# BRAIN_2.net
KiCad netlist of a schematic drawn in EAGLE
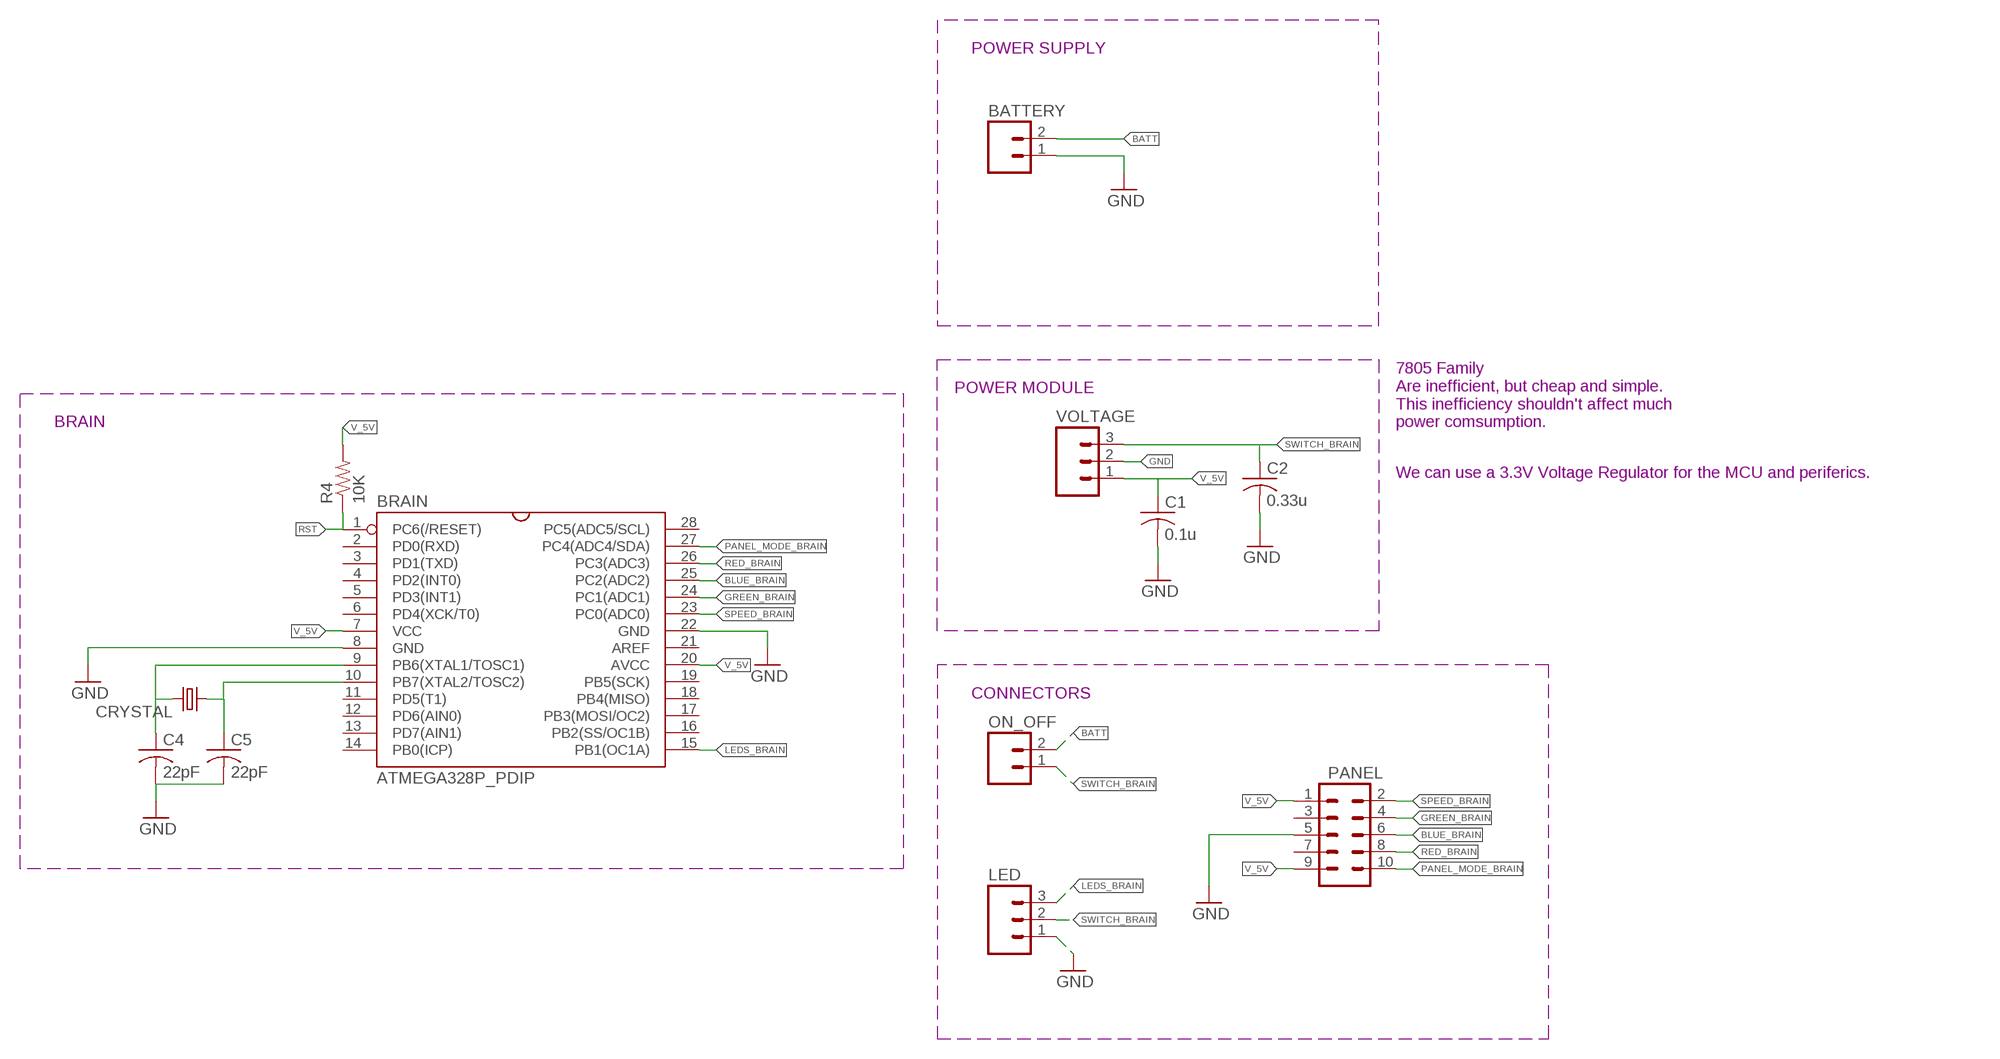
[diagram p0: schematic, sheet 1]

(export (version "E")
  (design (tool "Eeschema 10.0.6"))
  (components
    (comp (ref "BATTERY")
      (value "M02PTH")
      (footprint "eagle-import:1X02")
      (libsource (lib "eagle-import") (part "M02PTH"))
    )
    (comp (ref "BRAIN")
      (value "ATMEGA328P_PDIP")
      (footprint "eagle-import:DIL-28-3")
      (libsource (lib "eagle-import") (part "ATMEGA328P_PDIP"))
    )
    (comp (ref "C1")
      (value "0.1u")
      (footprint "eagle-import:C025-025X050")
      (libsource (lib "eagle-import") (part "C-US025-025X050"))
    )
    (comp (ref "C2")
      (value "0.33u")
      (footprint "eagle-import:C025-025X050")
      (libsource (lib "eagle-import") (part "C-US025-025X050"))
    )
    (comp (ref "C4")
      (value "22pF")
      (footprint "eagle-import:C025-024X044")
      (libsource (lib "eagle-import") (part "C-US025-024X044"))
    )
    (comp (ref "C5")
      (value "22pF")
      (footprint "eagle-import:C025-024X044")
      (libsource (lib "eagle-import") (part "C-US025-024X044"))
    )
    (comp (ref "CRYSTAL")
      (value "CRYSTALHC49US")
      (footprint "eagle-import:HC49US")
      (libsource (lib "eagle-import") (part "CRYSTALHC49US"))
    )
    (comp (ref "LED")
      (value "M03JST-PTH")
      (footprint "eagle-import:JST-3-PTH")
      (libsource (lib "eagle-import") (part "M03JST-PTH"))
    )
    (comp (ref "ON_OFF")
      (value "M02-JST-2-PTH-NO_SILK")
      (footprint "eagle-import:JST-2-PTH-NS")
      (libsource (lib "eagle-import") (part "M02-JST-2-PTH-NO_SILK"))
    )
    (comp (ref "PANEL")
      (value "M05X2SHD")
      (footprint "eagle-import:2X5-SHROUDED")
      (libsource (lib "eagle-import") (part "M05X2SHD"))
    )
    (comp (ref "R4")
      (value "10K")
      (footprint "eagle-import:1206")
      (libsource (lib "eagle-import") (part "RESISTOR1206"))
    )
    (comp (ref "VOLTAGE")
      (value "M03PTH")
      (footprint "eagle-import:1X03")
      (libsource (lib "eagle-import") (part "M03PTH"))
    )
  )
  (nets
    (net (code "1") (name "BATT") (class "Default")
      (node (ref "BATTERY") (pin "2") (pinfunction "2_2") (pintype "passive"))
      (node (ref "ON_OFF") (pin "2") (pinfunction "2_2") (pintype "passive"))
    )
    (net (code "2") (name "BLUE_BRAIN") (class "Default")
      (node (ref "BRAIN") (pin "25") (pinfunction "PC2(ADC2)_25") (pintype "bidirectional"))
      (node (ref "PANEL") (pin "6") (pinfunction "6_6") (pintype "passive"))
    )
    (net (code "3") (name "GND") (class "Default")
      (node (ref "BATTERY") (pin "1") (pinfunction "1_1") (pintype "passive"))
      (node (ref "BRAIN") (pin "22") (pinfunction "GND_22") (pintype "bidirectional"))
      (node (ref "BRAIN") (pin "8") (pinfunction "GND_8") (pintype "bidirectional"))
      (node (ref "C1") (pin "2") (pinfunction "2_2") (pintype "passive"))
      (node (ref "C2") (pin "2") (pinfunction "2_2") (pintype "passive"))
      (node (ref "C4") (pin "2") (pinfunction "2_2") (pintype "passive"))
      (node (ref "C5") (pin "2") (pinfunction "2_2") (pintype "passive"))
      (node (ref "LED") (pin "1") (pinfunction "1_1") (pintype "passive"))
      (node (ref "PANEL") (pin "5") (pinfunction "5_5") (pintype "passive"))
      (node (ref "VOLTAGE") (pin "2") (pinfunction "2_2") (pintype "passive"))
    )
    (net (code "4") (name "GREEN_BRAIN") (class "Default")
      (node (ref "BRAIN") (pin "24") (pinfunction "PC1(ADC1)_24") (pintype "bidirectional"))
      (node (ref "PANEL") (pin "4") (pinfunction "4_4") (pintype "passive"))
    )
    (net (code "5") (name "LEDS_BRAIN") (class "Default")
      (node (ref "BRAIN") (pin "15") (pinfunction "PB1(OC1A)_15") (pintype "bidirectional"))
      (node (ref "LED") (pin "3") (pinfunction "3_3") (pintype "passive"))
    )
    (net (code "6") (name "Net-(BRAIN-PB6(XTAL1{slash}TOSC1))") (class "Default")
      (node (ref "BRAIN") (pin "9") (pinfunction "PB6(XTAL1/TOSC1)_9") (pintype "bidirectional"))
      (node (ref "C4") (pin "1") (pinfunction "1_1") (pintype "passive"))
      (node (ref "CRYSTAL") (pin "2") (pinfunction "2_2") (pintype "passive"))
    )
    (net (code "7") (name "Net-(BRAIN-PB7(XTAL2{slash}TOSC2))") (class "Default")
      (node (ref "BRAIN") (pin "10") (pinfunction "PB7(XTAL2/TOSC2)_10") (pintype "bidirectional"))
      (node (ref "C5") (pin "1") (pinfunction "1_1") (pintype "passive"))
      (node (ref "CRYSTAL") (pin "1") (pinfunction "1_1") (pintype "passive"))
    )
    (net (code "8") (name "PANEL_MODE_BRAIN") (class "Default")
      (node (ref "BRAIN") (pin "27") (pinfunction "PC4(ADC4/SDA)_27") (pintype "bidirectional"))
      (node (ref "PANEL") (pin "10") (pinfunction "10_10") (pintype "passive"))
    )
    (net (code "9") (name "RED_BRAIN") (class "Default")
      (node (ref "BRAIN") (pin "26") (pinfunction "PC3(ADC3)_26") (pintype "bidirectional"))
      (node (ref "PANEL") (pin "8") (pinfunction "8_8") (pintype "passive"))
    )
    (net (code "10") (name "RST") (class "Default")
      (node (ref "BRAIN") (pin "1") (pinfunction "PC6(/RESET)_1") (pintype "bidirectional"))
      (node (ref "R4") (pin "1") (pinfunction "1_1") (pintype "passive"))
    )
    (net (code "11") (name "SPEED_BRAIN") (class "Default")
      (node (ref "BRAIN") (pin "23") (pinfunction "PC0(ADC0)_23") (pintype "bidirectional"))
      (node (ref "PANEL") (pin "2") (pinfunction "2_2") (pintype "passive"))
    )
    (net (code "12") (name "SWITCH_BRAIN") (class "Default")
      (node (ref "C2") (pin "1") (pinfunction "1_1") (pintype "passive"))
      (node (ref "LED") (pin "2") (pinfunction "2_2") (pintype "passive"))
      (node (ref "ON_OFF") (pin "1") (pinfunction "1_1") (pintype "passive"))
      (node (ref "VOLTAGE") (pin "3") (pinfunction "3_3") (pintype "passive"))
    )
    (net (code "13") (name "V_5V") (class "Default")
      (node (ref "BRAIN") (pin "20") (pinfunction "AVCC_20") (pintype "bidirectional"))
      (node (ref "BRAIN") (pin "7") (pinfunction "VCC_7") (pintype "bidirectional"))
      (node (ref "C1") (pin "1") (pinfunction "1_1") (pintype "passive"))
      (node (ref "PANEL") (pin "1") (pinfunction "1_1") (pintype "passive"))
      (node (ref "PANEL") (pin "9") (pinfunction "9_9") (pintype "passive"))
      (node (ref "R4") (pin "2") (pinfunction "2_2") (pintype "passive"))
      (node (ref "VOLTAGE") (pin "1") (pinfunction "1_1") (pintype "passive"))
    )
    (net (code "14") (name "unconnected-(BRAIN-AREF-Pad21)") (class "Default")
      (node (ref "BRAIN") (pin "21") (pinfunction "AREF_21") (pintype "bidirectional"))
    )
    (net (code "15") (name "unconnected-(BRAIN-PB0(ICP)-Pad14)") (class "Default")
      (node (ref "BRAIN") (pin "14") (pinfunction "PB0(ICP)_14") (pintype "bidirectional"))
    )
    (net (code "16") (name "unconnected-(BRAIN-PB2(SS{slash}OC1B)-Pad16)") (class "Default")
      (node (ref "BRAIN") (pin "16") (pinfunction "PB2(SS/OC1B)_16") (pintype "bidirectional"))
    )
    (net (code "17") (name "unconnected-(BRAIN-PB3(MOSI{slash}OC2)-Pad17)") (class "Default")
      (node (ref "BRAIN") (pin "17") (pinfunction "PB3(MOSI/OC2)_17") (pintype "bidirectional"))
    )
    (net (code "18") (name "unconnected-(BRAIN-PB4(MISO)-Pad18)") (class "Default")
      (node (ref "BRAIN") (pin "18") (pinfunction "PB4(MISO)_18") (pintype "bidirectional"))
    )
    (net (code "19") (name "unconnected-(BRAIN-PB5(SCK)-Pad19)") (class "Default")
      (node (ref "BRAIN") (pin "19") (pinfunction "PB5(SCK)_19") (pintype "bidirectional"))
    )
    (net (code "20") (name "unconnected-(BRAIN-PC5(ADC5{slash}SCL)-Pad28)") (class "Default")
      (node (ref "BRAIN") (pin "28") (pinfunction "PC5(ADC5/SCL)_28") (pintype "bidirectional"))
    )
    (net (code "21") (name "unconnected-(BRAIN-PD0(RXD)-Pad2)") (class "Default")
      (node (ref "BRAIN") (pin "2") (pinfunction "PD0(RXD)_2") (pintype "bidirectional"))
    )
    (net (code "22") (name "unconnected-(BRAIN-PD1(TXD)-Pad3)") (class "Default")
      (node (ref "BRAIN") (pin "3") (pinfunction "PD1(TXD)_3") (pintype "bidirectional"))
    )
    (net (code "23") (name "unconnected-(BRAIN-PD2(INT0)-Pad4)") (class "Default")
      (node (ref "BRAIN") (pin "4") (pinfunction "PD2(INT0)_4") (pintype "bidirectional"))
    )
    (net (code "24") (name "unconnected-(BRAIN-PD3(INT1)-Pad5)") (class "Default")
      (node (ref "BRAIN") (pin "5") (pinfunction "PD3(INT1)_5") (pintype "bidirectional"))
    )
    (net (code "25") (name "unconnected-(BRAIN-PD4(XCK{slash}T0)-Pad6)") (class "Default")
      (node (ref "BRAIN") (pin "6") (pinfunction "PD4(XCK/T0)_6") (pintype "bidirectional"))
    )
    (net (code "26") (name "unconnected-(BRAIN-PD5(T1)-Pad11)") (class "Default")
      (node (ref "BRAIN") (pin "11") (pinfunction "PD5(T1)_11") (pintype "bidirectional"))
    )
    (net (code "27") (name "unconnected-(BRAIN-PD6(AIN0)-Pad12)") (class "Default")
      (node (ref "BRAIN") (pin "12") (pinfunction "PD6(AIN0)_12") (pintype "bidirectional"))
    )
    (net (code "28") (name "unconnected-(BRAIN-PD7(AIN1)-Pad13)") (class "Default")
      (node (ref "BRAIN") (pin "13") (pinfunction "PD7(AIN1)_13") (pintype "bidirectional"))
    )
    (net (code "29") (name "unconnected-(PANEL-Pad3)") (class "Default")
      (node (ref "PANEL") (pin "3") (pinfunction "3_3") (pintype "passive"))
    )
    (net (code "30") (name "unconnected-(PANEL-Pad7)") (class "Default")
      (node (ref "PANEL") (pin "7") (pinfunction "7_7") (pintype "passive"))
    )
  )
)
